# Sheet1.net
KiCad netlist of a schematic drawn in Altium Designer
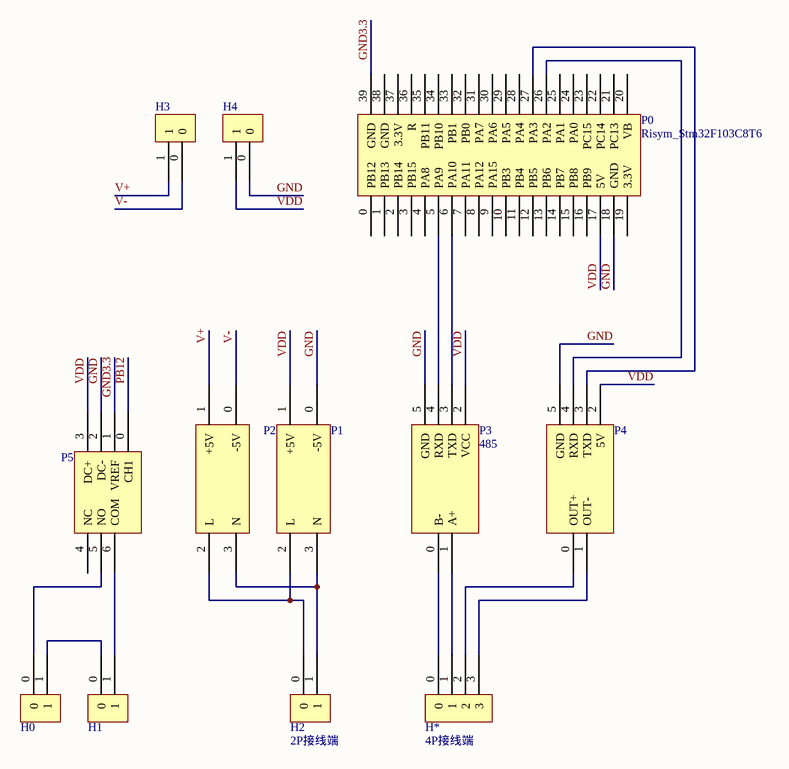
[diagram p0: Sheet1.SchDoc]

(export (version "E")
  (design (tool "Eeschema 10.0.6"))
  (components
    (comp (ref "H*")
      (value "4P接线端")
      (description "5.08-1mm")
      (libsource (lib "Integrated_Library1") (part "4P接线端"))
    )
    (comp (ref "H0")
      (value "2P接线端")
      (description "5.08-1mm")
      (libsource (lib "Integrated_Library1") (part "2P接线端"))
    )
    (comp (ref "H1")
      (value "2P接线端")
      (description "5.08-1mm")
      (libsource (lib "Integrated_Library1") (part "2P接线端"))
    )
    (comp (ref "H2")
      (value "2P接线端")
      (description "5.08-1mm")
      (libsource (lib "Integrated_Library1") (part "2P接线端"))
    )
    (comp (ref "H3") (value "2P接线端") (description "5.08-1mm") (libsource (lib "") (part "2P接线端_1")))
    (comp (ref "H4") (value "2P接线端") (description "5.08-1mm") (libsource (lib "") (part "2P接线端_1")))
    (comp (ref "P0")
      (value "Risym_Stm32F103C8T6")
      (libsource (lib "Integrated_Library1") (part "Risym_Stm32F103C8T6"))
    )
    (comp (ref "P1")
      (value "AC-DC隔离电源-220-5")
      (libsource (lib "Integrated_Library1") (part "AC-DC隔离电源-220-5"))
    )
    (comp (ref "P2")
      (value "AC-DC隔离电源-220-5")
      (libsource (lib "Integrated_Library1") (part "AC-DC隔离电源-220-5"))
    )
    (comp (ref "P3") (value "485") (libsource (lib "Integrated_Library1") (part "485")))
    (comp (ref "P4") (value "YS-IR02F") (libsource (lib "Integrated_Library1") (part "YS-IR02F")))
    (comp (ref "P5")
      (value "Risym_光耦隔离继电器5V")
      (libsource (lib "Integrated_Library1") (part "Risym_光耦隔离继电器5V"))
    )
  )
  (nets
    (net (code "1") (name "/GND") (class "Default")
      (node (ref "H4") (pin "0") (pinfunction "0_0") (pintype "passive"))
      (node (ref "P0") (pin "18") (pinfunction "GND_18") (pintype "passive"))
      (node (ref "P1") (pin "0") (pinfunction "-5V_0") (pintype "passive"))
      (node (ref "P3") (pin "5") (pinfunction "GND_5") (pintype "passive"))
      (node (ref "P4") (pin "5") (pinfunction "GND_5") (pintype "passive"))
      (node (ref "P5") (pin "2") (pinfunction "DC-_2") (pintype "passive"))
    )
    (net (code "2") (name "/GND3.3") (class "Default")
      (node (ref "P0") (pin "39") (pinfunction "GND_39") (pintype "passive"))
      (node (ref "P5") (pin "1") (pinfunction "VREF_1") (pintype "passive"))
    )
    (net (code "3") (name "/PB12") (class "Default")
      (node (ref "P5") (pin "0") (pinfunction "CH1_0") (pintype "passive"))
    )
    (net (code "4") (name "/V+") (class "Default")
      (node (ref "H3") (pin "1") (pinfunction "1_1") (pintype "passive"))
      (node (ref "P2") (pin "1") (pinfunction "+5V_1") (pintype "passive"))
    )
    (net (code "5") (name "/V-") (class "Default")
      (node (ref "H3") (pin "0") (pinfunction "0_0") (pintype "passive"))
      (node (ref "P2") (pin "0") (pinfunction "-5V_0") (pintype "passive"))
    )
    (net (code "6") (name "/VDD") (class "Default")
      (node (ref "H4") (pin "1") (pinfunction "1_1") (pintype "passive"))
      (node (ref "P0") (pin "17") (pinfunction "5V_17") (pintype "passive"))
      (node (ref "P1") (pin "1") (pinfunction "+5V_1") (pintype "passive"))
      (node (ref "P3") (pin "2") (pinfunction "VCC_2") (pintype "passive"))
      (node (ref "P4") (pin "2") (pinfunction "5V_2") (pintype "passive"))
      (node (ref "P5") (pin "3") (pinfunction "DC+_3") (pintype "passive"))
    )
    (net (code "7") (name "Net-(H0-Pad1)") (class "Default")
      (node (ref "H0") (pin "1") (pinfunction "1_1") (pintype "passive"))
      (node (ref "H1") (pin "0") (pinfunction "0_0") (pintype "passive"))
    )
    (net (code "8") (name "Net-(P0-PA2)") (class "Default")
      (node (ref "P0") (pin "26") (pinfunction "PA2_26") (pintype "passive"))
      (node (ref "P4") (pin "4") (pinfunction "RXD_4") (pintype "passive"))
    )
    (net (code "9") (name "Net-(P0-PA3)") (class "Default")
      (node (ref "P0") (pin "27") (pinfunction "PA3_27") (pintype "passive"))
      (node (ref "P4") (pin "3") (pinfunction "TXD_3") (pintype "passive"))
    )
    (net (code "10") (name "Net-(P0-PA9)") (class "Default")
      (node (ref "P0") (pin "5") (pinfunction "PA9_5") (pintype "passive"))
      (node (ref "P3") (pin "4") (pinfunction "RXD_4") (pintype "passive"))
    )
    (net (code "11") (name "Net-(P0-PA10)") (class "Default")
      (node (ref "P0") (pin "6") (pinfunction "PA10_6") (pintype "passive"))
      (node (ref "P3") (pin "3") (pinfunction "TXD_3") (pintype "passive"))
    )
    (net (code "12") (name "Net-(P1-L)") (class "Default")
      (node (ref "H2") (pin "0") (pinfunction "0_0") (pintype "passive"))
      (node (ref "P1") (pin "2") (pinfunction "L_2") (pintype "passive"))
      (node (ref "P2") (pin "2") (pinfunction "L_2") (pintype "passive"))
    )
    (net (code "13") (name "Net-(P1-N)") (class "Default")
      (node (ref "H2") (pin "1") (pinfunction "1_1") (pintype "passive"))
      (node (ref "P1") (pin "3") (pinfunction "N_3") (pintype "passive"))
      (node (ref "P2") (pin "3") (pinfunction "N_3") (pintype "passive"))
    )
    (net (code "14") (name "Net-(P3-A+)") (class "Default")
      (node (ref "H*") (pin "1") (pinfunction "1_1") (pintype "passive"))
      (node (ref "P3") (pin "1") (pinfunction "A+_1") (pintype "passive"))
    )
    (net (code "15") (name "Net-(P3-B-)") (class "Default")
      (node (ref "H*") (pin "0") (pinfunction "0_0") (pintype "passive"))
      (node (ref "P3") (pin "0") (pinfunction "B-_0") (pintype "passive"))
    )
    (net (code "16") (name "Net-(P4-OUT+)") (class "Default")
      (node (ref "H*") (pin "2") (pinfunction "2_2") (pintype "passive"))
      (node (ref "P4") (pin "0") (pinfunction "OUT+_0") (pintype "passive"))
    )
    (net (code "17") (name "Net-(P4-OUT-)") (class "Default")
      (node (ref "H*") (pin "3") (pinfunction "3_3") (pintype "passive"))
      (node (ref "P4") (pin "1") (pinfunction "OUT-_1") (pintype "passive"))
    )
    (net (code "18") (name "Net-(P5-COM)") (class "Default")
      (node (ref "H1") (pin "1") (pinfunction "1_1") (pintype "passive"))
      (node (ref "P5") (pin "6") (pinfunction "COM_6") (pintype "passive"))
    )
    (net (code "19") (name "Net-(P5-NO)") (class "Default")
      (node (ref "H0") (pin "0") (pinfunction "0_0") (pintype "passive"))
      (node (ref "P5") (pin "5") (pinfunction "NO_5") (pintype "passive"))
    )
    (net (code "20") (name "unconnected-(P0-3.3V-Pad19)") (class "Default")
      (node (ref "P0") (pin "19") (pinfunction "3.3V_19") (pintype "passive"))
    )
    (net (code "21") (name "unconnected-(P0-3.3V-Pad37)") (class "Default")
      (node (ref "P0") (pin "37") (pinfunction "3.3V_37") (pintype "passive"))
    )
    (net (code "22") (name "unconnected-(P0-GND-Pad38)") (class "Default")
      (node (ref "P0") (pin "38") (pinfunction "GND_38") (pintype "passive"))
    )
    (net (code "23") (name "unconnected-(P0-PA0-Pad24)") (class "Default")
      (node (ref "P0") (pin "24") (pinfunction "PA0_24") (pintype "passive"))
    )
    (net (code "24") (name "unconnected-(P0-PA1-Pad25)") (class "Default")
      (node (ref "P0") (pin "25") (pinfunction "PA1_25") (pintype "passive"))
    )
    (net (code "25") (name "unconnected-(P0-PA4-Pad28)") (class "Default")
      (node (ref "P0") (pin "28") (pinfunction "PA4_28") (pintype "passive"))
    )
    (net (code "26") (name "unconnected-(P0-PA5-Pad29)") (class "Default")
      (node (ref "P0") (pin "29") (pinfunction "PA5_29") (pintype "passive"))
    )
    (net (code "27") (name "unconnected-(P0-PA6-Pad30)") (class "Default")
      (node (ref "P0") (pin "30") (pinfunction "PA6_30") (pintype "passive"))
    )
    (net (code "28") (name "unconnected-(P0-PA7-Pad31)") (class "Default")
      (node (ref "P0") (pin "31") (pinfunction "PA7_31") (pintype "passive"))
    )
    (net (code "29") (name "unconnected-(P0-PA8-Pad4)") (class "Default")
      (node (ref "P0") (pin "4") (pinfunction "PA8_4") (pintype "passive"))
    )
    (net (code "30") (name "unconnected-(P0-PA11-Pad7)") (class "Default")
      (node (ref "P0") (pin "7") (pinfunction "PA11_7") (pintype "passive"))
    )
    (net (code "31") (name "unconnected-(P0-PA12-Pad8)") (class "Default")
      (node (ref "P0") (pin "8") (pinfunction "PA12_8") (pintype "passive"))
    )
    (net (code "32") (name "unconnected-(P0-PA15-Pad9)") (class "Default")
      (node (ref "P0") (pin "9") (pinfunction "PA15_9") (pintype "passive"))
    )
    (net (code "33") (name "unconnected-(P0-PB0-Pad32)") (class "Default")
      (node (ref "P0") (pin "32") (pinfunction "PB0_32") (pintype "passive"))
    )
    (net (code "34") (name "unconnected-(P0-PB1-Pad33)") (class "Default")
      (node (ref "P0") (pin "33") (pinfunction "PB1_33") (pintype "passive"))
    )
    (net (code "35") (name "unconnected-(P0-PB3-Pad10)") (class "Default")
      (node (ref "P0") (pin "10") (pinfunction "PB3_10") (pintype "passive"))
    )
    (net (code "36") (name "unconnected-(P0-PB4-Pad11)") (class "Default")
      (node (ref "P0") (pin "11") (pinfunction "PB4_11") (pintype "passive"))
    )
    (net (code "37") (name "unconnected-(P0-PB5-Pad12)") (class "Default")
      (node (ref "P0") (pin "12") (pinfunction "PB5_12") (pintype "passive"))
    )
    (net (code "38") (name "unconnected-(P0-PB6-Pad13)") (class "Default")
      (node (ref "P0") (pin "13") (pinfunction "PB6_13") (pintype "passive"))
    )
    (net (code "39") (name "unconnected-(P0-PB7-Pad14)") (class "Default")
      (node (ref "P0") (pin "14") (pinfunction "PB7_14") (pintype "passive"))
    )
    (net (code "40") (name "unconnected-(P0-PB8-Pad15)") (class "Default")
      (node (ref "P0") (pin "15") (pinfunction "PB8_15") (pintype "passive"))
    )
    (net (code "41") (name "unconnected-(P0-PB9-Pad16)") (class "Default")
      (node (ref "P0") (pin "16") (pinfunction "PB9_16") (pintype "passive"))
    )
    (net (code "42") (name "unconnected-(P0-PB10-Pad34)") (class "Default")
      (node (ref "P0") (pin "34") (pinfunction "PB10_34") (pintype "passive"))
    )
    (net (code "43") (name "unconnected-(P0-PB11-Pad35)") (class "Default")
      (node (ref "P0") (pin "35") (pinfunction "PB11_35") (pintype "passive"))
    )
    (net (code "44") (name "unconnected-(P0-PB12-Pad0)") (class "Default")
      (node (ref "P0") (pin "0") (pinfunction "PB12_0") (pintype "passive"))
    )
    (net (code "45") (name "unconnected-(P0-PB13-Pad1)") (class "Default")
      (node (ref "P0") (pin "1") (pinfunction "PB13_1") (pintype "passive"))
    )
    (net (code "46") (name "unconnected-(P0-PB14-Pad2)") (class "Default")
      (node (ref "P0") (pin "2") (pinfunction "PB14_2") (pintype "passive"))
    )
    (net (code "47") (name "unconnected-(P0-PB15-Pad3)") (class "Default")
      (node (ref "P0") (pin "3") (pinfunction "PB15_3") (pintype "passive"))
    )
    (net (code "48") (name "unconnected-(P0-PC13-Pad21)") (class "Default")
      (node (ref "P0") (pin "21") (pinfunction "PC13_21") (pintype "passive"))
    )
    (net (code "49") (name "unconnected-(P0-PC14-Pad22)") (class "Default")
      (node (ref "P0") (pin "22") (pinfunction "PC14_22") (pintype "passive"))
    )
    (net (code "50") (name "unconnected-(P0-PC15-Pad23)") (class "Default")
      (node (ref "P0") (pin "23") (pinfunction "PC15_23") (pintype "passive"))
    )
    (net (code "51") (name "unconnected-(P0-R-Pad36)") (class "Default")
      (node (ref "P0") (pin "36") (pinfunction "R_36") (pintype "passive"))
    )
    (net (code "52") (name "unconnected-(P0-VB-Pad20)") (class "Default")
      (node (ref "P0") (pin "20") (pinfunction "VB_20") (pintype "passive"))
    )
    (net (code "53") (name "unconnected-(P5-NC-Pad4)") (class "Default")
      (node (ref "P5") (pin "4") (pinfunction "NC_4") (pintype "passive"))
    )
  )
)
